# isolatedPowerSerial.net
KiCad netlist of a schematic drawn in EAGLE
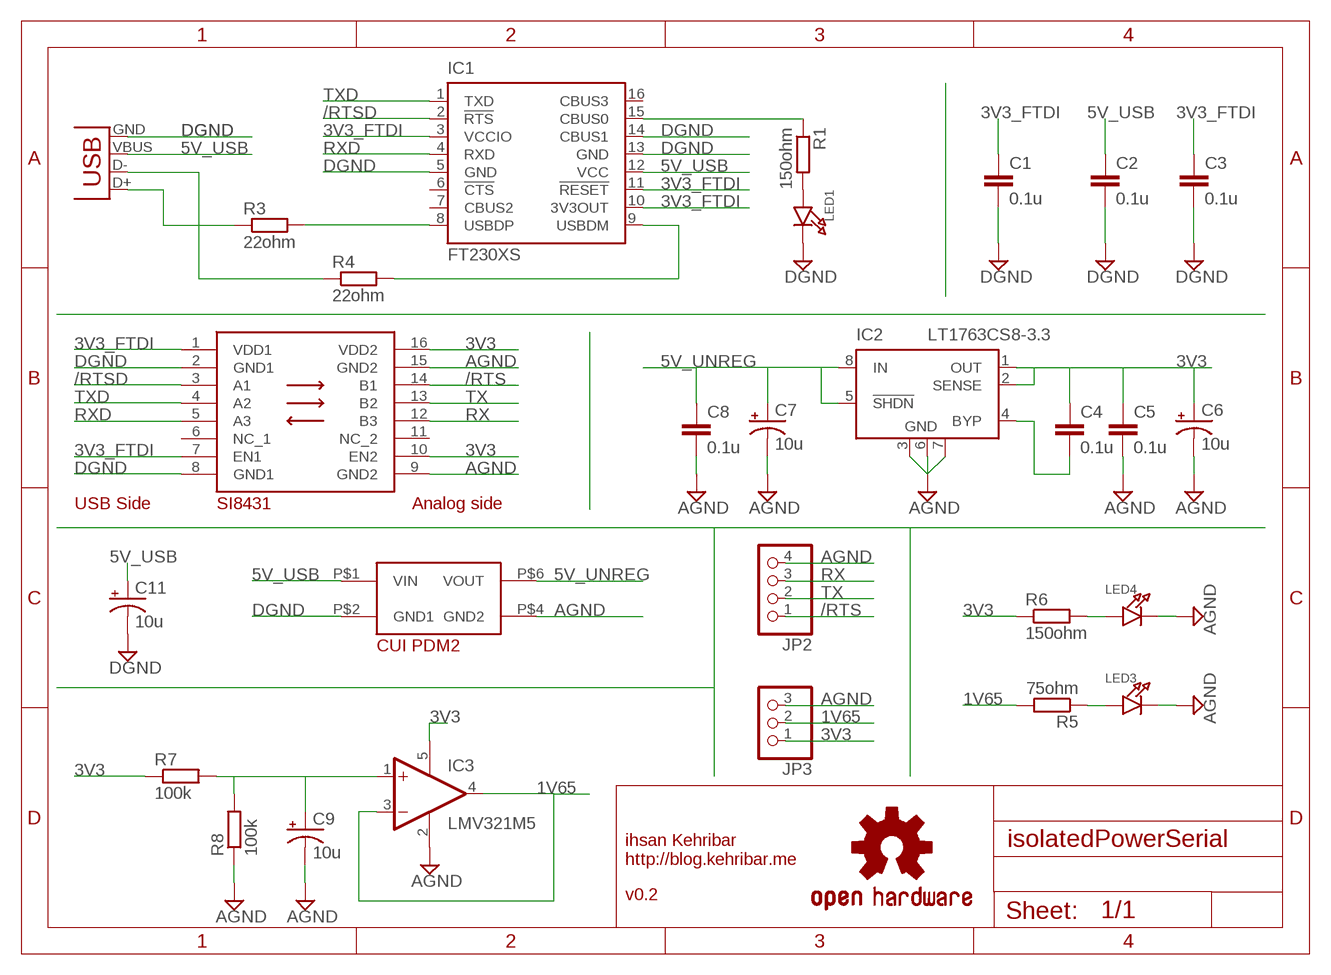
[diagram p0: schematic, sheet 1]

(export (version "E")
  (design (tool "Eeschema 10.0.6"))
  (components
    (comp (ref "C1")
      (value "0.1u")
      (footprint "eagle-import:C0805")
      (libsource (lib "eagle-import") (part "C-EUC0805"))
    )
    (comp (ref "C2")
      (value "0.1u")
      (footprint "eagle-import:C0805")
      (libsource (lib "eagle-import") (part "C-EUC0805"))
    )
    (comp (ref "C3")
      (value "0.1u")
      (footprint "eagle-import:C0805")
      (libsource (lib "eagle-import") (part "C-EUC0805"))
    )
    (comp (ref "C4")
      (value "0.1u")
      (footprint "eagle-import:C0805")
      (libsource (lib "eagle-import") (part "C-EUC0805"))
    )
    (comp (ref "C5")
      (value "0.1u")
      (footprint "eagle-import:C0805")
      (libsource (lib "eagle-import") (part "C-EUC0805"))
    )
    (comp (ref "C6")
      (value "10u")
      (footprint "eagle-import:B_3528-21R")
      (libsource (lib "eagle-import") (part "CPOL-USB/3528-21R"))
    )
    (comp (ref "C7")
      (value "10u")
      (footprint "eagle-import:B_3528-21R")
      (libsource (lib "eagle-import") (part "CPOL-USB/3528-21R"))
    )
    (comp (ref "C8")
      (value "0.1u")
      (footprint "eagle-import:C0805")
      (libsource (lib "eagle-import") (part "C-EUC0805"))
    )
    (comp (ref "C9")
      (value "10u")
      (footprint "eagle-import:B_3528-21R")
      (libsource (lib "eagle-import") (part "CPOL-USB/3528-21R"))
    )
    (comp (ref "C11")
      (value "10u")
      (footprint "eagle-import:B_3528-21R")
      (libsource (lib "eagle-import") (part "CPOL-USB/3528-21R"))
    )
    (comp (ref "IC1")
      (value "FT230XS")
      (footprint "eagle-import:SSOP16")
      (libsource (lib "eagle-import") (part "FT230XS"))
    )
    (comp (ref "IC2")
      (value "LT1763CS8-3.3")
      (footprint "eagle-import:SOIC8")
      (libsource (lib "eagle-import") (part "LT1763CS8-3.3"))
    )
    (comp (ref "IC3")
      (value "LMV321M5")
      (footprint "eagle-import:SOT23-5")
      (libsource (lib "eagle-import") (part "LMV321?M5"))
    )
    (comp (ref "JP1")
      (value "USBSMD")
      (footprint "eagle-import:USB-MINIB")
      (libsource (lib "eagle-import") (part "USBSMD"))
    )
    (comp (ref "JP2")
      (value "HEADER-1X4ROUND")
      (footprint "eagle-import:1X04_ROUND")
      (libsource (lib "eagle-import") (part "HEADER-1X4ROUND"))
    )
    (comp (ref "JP3")
      (value "HEADER-1X3ROUND")
      (footprint "eagle-import:1X03_ROUND")
      (libsource (lib "eagle-import") (part "HEADER-1X3ROUND"))
    )
    (comp (ref "LED1")
      (value "LED0805")
      (footprint "eagle-import:CHIPLED_0805")
      (libsource (lib "eagle-import") (part "LED0805"))
    )
    (comp (ref "LED3")
      (value "LED0805")
      (footprint "eagle-import:CHIPLED_0805")
      (libsource (lib "eagle-import") (part "LED0805"))
    )
    (comp (ref "LED4")
      (value "LED0805")
      (footprint "eagle-import:CHIPLED_0805")
      (libsource (lib "eagle-import") (part "LED0805"))
    )
    (comp (ref "LOGO1")
      (value "OSHW-LOGOS")
      (footprint "eagle-import:OSHW-LOGO-S")
      (libsource (lib "eagle-import") (part "OSHW-LOGOS"))
    )
    (comp (ref "R1")
      (value "150ohm")
      (footprint "eagle-import:R0805")
      (libsource (lib "eagle-import") (part "R-EU_R0805"))
    )
    (comp (ref "R3")
      (value "22ohm")
      (footprint "eagle-import:R0805")
      (libsource (lib "eagle-import") (part "R-EU_R0805"))
    )
    (comp (ref "R4")
      (value "22ohm")
      (footprint "eagle-import:R0805")
      (libsource (lib "eagle-import") (part "R-EU_R0805"))
    )
    (comp (ref "R5")
      (value "75ohm")
      (footprint "eagle-import:R0805")
      (libsource (lib "eagle-import") (part "R-EU_R0805"))
    )
    (comp (ref "R6")
      (value "150ohm")
      (footprint "eagle-import:R0805")
      (libsource (lib "eagle-import") (part "R-EU_R0805"))
    )
    (comp (ref "R7")
      (value "100k")
      (footprint "eagle-import:R0805")
      (libsource (lib "eagle-import") (part "R-EU_R0805"))
    )
    (comp (ref "R8")
      (value "100k")
      (footprint "eagle-import:R0805")
      (libsource (lib "eagle-import") (part "R-EU_R0805"))
    )
    (comp (ref "U$1")
      (value "IHSAN_SI8431")
      (footprint "eagle-import:SO16L")
      (libsource (lib "eagle-import") (part "IHSAN_SI8431"))
    )
    (comp (ref "U$2")
      (value "IHSAN_CUI_PDM2")
      (footprint "eagle-import:SIL7")
      (libsource (lib "eagle-import") (part "IHSAN_CUI_PDM2"))
    )
  )
  (nets
    (net (code "1") (name "/1V65") (class "Default")
      (node (ref "IC3") (pin "3") (pinfunction "-IN_3") (pintype "input"))
      (node (ref "IC3") (pin "4") (pinfunction "OUT_4") (pintype "output"))
      (node (ref "JP3") (pin "2") (pinfunction "2_2") (pintype "passive"))
      (node (ref "R5") (pin "2") (pinfunction "2_2") (pintype "passive"))
    )
    (net (code "2") (name "/3V3") (class "Default")
      (node (ref "C4") (pin "1") (pinfunction "1_1") (pintype "passive"))
      (node (ref "C5") (pin "1") (pinfunction "1_1") (pintype "passive"))
      (node (ref "C6") (pin "+") (pinfunction "+_+") (pintype "passive"))
      (node (ref "IC2") (pin "1") (pinfunction "OUT_1") (pintype "passive"))
      (node (ref "IC2") (pin "2") (pinfunction "SENSE_2") (pintype "input"))
      (node (ref "IC3") (pin "5") (pinfunction "V+_5") (pintype "power_in"))
      (node (ref "JP3") (pin "1") (pinfunction "1_1") (pintype "passive"))
      (node (ref "R6") (pin "1") (pinfunction "1_1") (pintype "passive"))
      (node (ref "R7") (pin "1") (pinfunction "1_1") (pintype "passive"))
      (node (ref "U$1") (pin "10") (pinfunction "EN2_10") (pintype "bidirectional"))
      (node (ref "U$1") (pin "16") (pinfunction "VDD2_16") (pintype "bidirectional"))
    )
    (net (code "3") (name "/3V3_FTDI") (class "Default")
      (node (ref "C1") (pin "1") (pinfunction "1_1") (pintype "passive"))
      (node (ref "C3") (pin "1") (pinfunction "1_1") (pintype "passive"))
      (node (ref "IC1") (pin "10") (pinfunction "3V3OUT_10") (pintype "output"))
      (node (ref "IC1") (pin "11") (pinfunction "~{RESET}_11") (pintype "input"))
      (node (ref "IC1") (pin "3") (pinfunction "VCCIO_3") (pintype "power_in"))
      (node (ref "U$1") (pin "1") (pinfunction "VDD1_1") (pintype "bidirectional"))
      (node (ref "U$1") (pin "7") (pinfunction "EN1_7") (pintype "bidirectional"))
    )
    (net (code "4") (name "/5V_UNREG") (class "Default")
      (node (ref "C7") (pin "+") (pinfunction "+_+") (pintype "passive"))
      (node (ref "C8") (pin "1") (pinfunction "1_1") (pintype "passive"))
      (node (ref "IC2") (pin "5") (pinfunction "~{SHDN}_5") (pintype "input"))
      (node (ref "IC2") (pin "8") (pinfunction "IN_8") (pintype "input"))
      (node (ref "U$2") (pin "P$6") (pinfunction "VOUT_P$6") (pintype "bidirectional"))
    )
    (net (code "5") (name "/5V_USB") (class "Default")
      (node (ref "C11") (pin "+") (pinfunction "+_+") (pintype "passive"))
      (node (ref "C2") (pin "1") (pinfunction "1_1") (pintype "passive"))
      (node (ref "IC1") (pin "12") (pinfunction "VCC_12") (pintype "power_in"))
      (node (ref "JP1") (pin "VBUS") (pinfunction "VBUS_VBUS") (pintype "bidirectional"))
      (node (ref "U$2") (pin "P$1") (pinfunction "VIN_P$1") (pintype "bidirectional"))
    )
    (net (code "6") (name "/RX") (class "Default")
      (node (ref "JP2") (pin "3") (pinfunction "3_3") (pintype "passive"))
      (node (ref "U$1") (pin "12") (pinfunction "B3_12") (pintype "bidirectional"))
    )
    (net (code "7") (name "/RXD") (class "Default")
      (node (ref "IC1") (pin "4") (pinfunction "RXD_4") (pintype "input"))
      (node (ref "U$1") (pin "5") (pinfunction "A3_5") (pintype "bidirectional"))
    )
    (net (code "8") (name "/TX") (class "Default")
      (node (ref "JP2") (pin "2") (pinfunction "2_2") (pintype "passive"))
      (node (ref "U$1") (pin "13") (pinfunction "B2_13") (pintype "bidirectional"))
    )
    (net (code "9") (name "/TXD") (class "Default")
      (node (ref "IC1") (pin "1") (pinfunction "TXD_1") (pintype "output"))
      (node (ref "U$1") (pin "4") (pinfunction "A2_4") (pintype "bidirectional"))
    )
    (net (code "10") (name "/{slash}RTS") (class "Default")
      (node (ref "JP2") (pin "1") (pinfunction "1_1") (pintype "passive"))
      (node (ref "U$1") (pin "14") (pinfunction "B1_14") (pintype "bidirectional"))
    )
    (net (code "11") (name "/{slash}RTSD") (class "Default")
      (node (ref "IC1") (pin "2") (pinfunction "~{RTS}_2") (pintype "output"))
      (node (ref "U$1") (pin "3") (pinfunction "A1_3") (pintype "bidirectional"))
    )
    (net (code "12") (name "AGND") (class "Default")
      (node (ref "C5") (pin "2") (pinfunction "2_2") (pintype "passive"))
      (node (ref "C6") (pin "-") (pinfunction "-_-") (pintype "passive"))
      (node (ref "C7") (pin "-") (pinfunction "-_-") (pintype "passive"))
      (node (ref "C8") (pin "2") (pinfunction "2_2") (pintype "passive"))
      (node (ref "C9") (pin "-") (pinfunction "-_-") (pintype "passive"))
      (node (ref "IC2") (pin "3") (pinfunction "GND_3") (pintype "power_in"))
      (node (ref "IC2") (pin "6") (pinfunction "GND_6") (pintype "power_in"))
      (node (ref "IC2") (pin "7") (pinfunction "GND_7") (pintype "power_in"))
      (node (ref "IC3") (pin "2") (pinfunction "V-_2") (pintype "power_in"))
      (node (ref "JP2") (pin "4") (pinfunction "4_4") (pintype "passive"))
      (node (ref "JP3") (pin "3") (pinfunction "3_3") (pintype "passive"))
      (node (ref "LED3") (pin "C") (pinfunction "C_C") (pintype "passive"))
      (node (ref "LED4") (pin "C") (pinfunction "C_C") (pintype "passive"))
      (node (ref "R8") (pin "1") (pinfunction "1_1") (pintype "passive"))
      (node (ref "U$1") (pin "15") (pinfunction "GND2_15") (pintype "bidirectional"))
      (node (ref "U$1") (pin "9") (pinfunction "GND2_9") (pintype "bidirectional"))
      (node (ref "U$2") (pin "P$4") (pinfunction "GND2_P$4") (pintype "bidirectional"))
    )
    (net (code "13") (name "DGND") (class "Default")
      (node (ref "C1") (pin "2") (pinfunction "2_2") (pintype "passive"))
      (node (ref "C11") (pin "-") (pinfunction "-_-") (pintype "passive"))
      (node (ref "C2") (pin "2") (pinfunction "2_2") (pintype "passive"))
      (node (ref "C3") (pin "2") (pinfunction "2_2") (pintype "passive"))
      (node (ref "IC1") (pin "13") (pinfunction "GND_13") (pintype "power_in"))
      (node (ref "IC1") (pin "14") (pinfunction "CBUS1_14") (pintype "bidirectional"))
      (node (ref "IC1") (pin "5") (pinfunction "GND_5") (pintype "power_in"))
      (node (ref "JP1") (pin "GND") (pinfunction "GND_GND") (pintype "bidirectional"))
      (node (ref "LED1") (pin "C") (pinfunction "C_C") (pintype "passive"))
      (node (ref "U$1") (pin "2") (pinfunction "GND1_2") (pintype "bidirectional"))
      (node (ref "U$1") (pin "8") (pinfunction "GND1_8") (pintype "bidirectional"))
      (node (ref "U$2") (pin "P$2") (pinfunction "GND1_P$2") (pintype "bidirectional"))
    )
    (net (code "14") (name "Net-(IC1-CBUS0)") (class "Default")
      (node (ref "IC1") (pin "15") (pinfunction "CBUS0_15") (pintype "bidirectional"))
      (node (ref "R1") (pin "1") (pinfunction "1_1") (pintype "passive"))
    )
    (net (code "15") (name "Net-(IC1-USBDM)") (class "Default")
      (node (ref "IC1") (pin "9") (pinfunction "USBDM_9") (pintype "input"))
      (node (ref "R4") (pin "2") (pinfunction "2_2") (pintype "passive"))
    )
    (net (code "16") (name "Net-(IC1-USBDP)") (class "Default")
      (node (ref "IC1") (pin "8") (pinfunction "USBDP_8") (pintype "input"))
      (node (ref "R3") (pin "2") (pinfunction "2_2") (pintype "passive"))
    )
    (net (code "17") (name "Net-(IC2-BYP)") (class "Default")
      (node (ref "C4") (pin "2") (pinfunction "2_2") (pintype "passive"))
      (node (ref "IC2") (pin "4") (pinfunction "BYP_4") (pintype "input"))
    )
    (net (code "18") (name "Net-(IC3-+IN)") (class "Default")
      (node (ref "C9") (pin "+") (pinfunction "+_+") (pintype "passive"))
      (node (ref "IC3") (pin "1") (pinfunction "+IN_1") (pintype "input"))
      (node (ref "R7") (pin "2") (pinfunction "2_2") (pintype "passive"))
      (node (ref "R8") (pin "2") (pinfunction "2_2") (pintype "passive"))
    )
    (net (code "19") (name "Net-(JP1-PadD+)") (class "Default")
      (node (ref "JP1") (pin "D+") (pinfunction "D+_D+") (pintype "bidirectional"))
      (node (ref "R3") (pin "1") (pinfunction "1_1") (pintype "passive"))
    )
    (net (code "20") (name "Net-(JP1-PadD-)") (class "Default")
      (node (ref "JP1") (pin "D-") (pinfunction "D-_D-") (pintype "bidirectional"))
      (node (ref "R4") (pin "1") (pinfunction "1_1") (pintype "passive"))
    )
    (net (code "21") (name "Net-(LED1-PadA)") (class "Default")
      (node (ref "LED1") (pin "A") (pinfunction "A_A") (pintype "passive"))
      (node (ref "R1") (pin "2") (pinfunction "2_2") (pintype "passive"))
    )
    (net (code "22") (name "Net-(LED3-PadA)") (class "Default")
      (node (ref "LED3") (pin "A") (pinfunction "A_A") (pintype "passive"))
      (node (ref "R5") (pin "1") (pinfunction "1_1") (pintype "passive"))
    )
    (net (code "23") (name "Net-(LED4-PadA)") (class "Default")
      (node (ref "LED4") (pin "A") (pinfunction "A_A") (pintype "passive"))
      (node (ref "R6") (pin "2") (pinfunction "2_2") (pintype "passive"))
    )
    (net (code "24") (name "unconnected-(IC1-CBUS2-Pad7)") (class "Default")
      (node (ref "IC1") (pin "7") (pinfunction "CBUS2_7") (pintype "bidirectional"))
    )
    (net (code "25") (name "unconnected-(IC1-CBUS3-Pad16)") (class "Default")
      (node (ref "IC1") (pin "16") (pinfunction "CBUS3_16") (pintype "bidirectional"))
    )
    (net (code "26") (name "unconnected-(IC1-~{CTS}-Pad6)") (class "Default")
      (node (ref "IC1") (pin "6") (pinfunction "~{CTS}_6") (pintype "input"))
    )
    (net (code "27") (name "unconnected-(U$1-NC_1-Pad6)") (class "Default")
      (node (ref "U$1") (pin "6") (pinfunction "NC_1_6") (pintype "bidirectional"))
    )
    (net (code "28") (name "unconnected-(U$1-NC_2-Pad11)") (class "Default")
      (node (ref "U$1") (pin "11") (pinfunction "NC_2_11") (pintype "bidirectional"))
    )
  )
)
